# CP2102N.net
KiCad netlist of a schematic drawn in Altium Designer
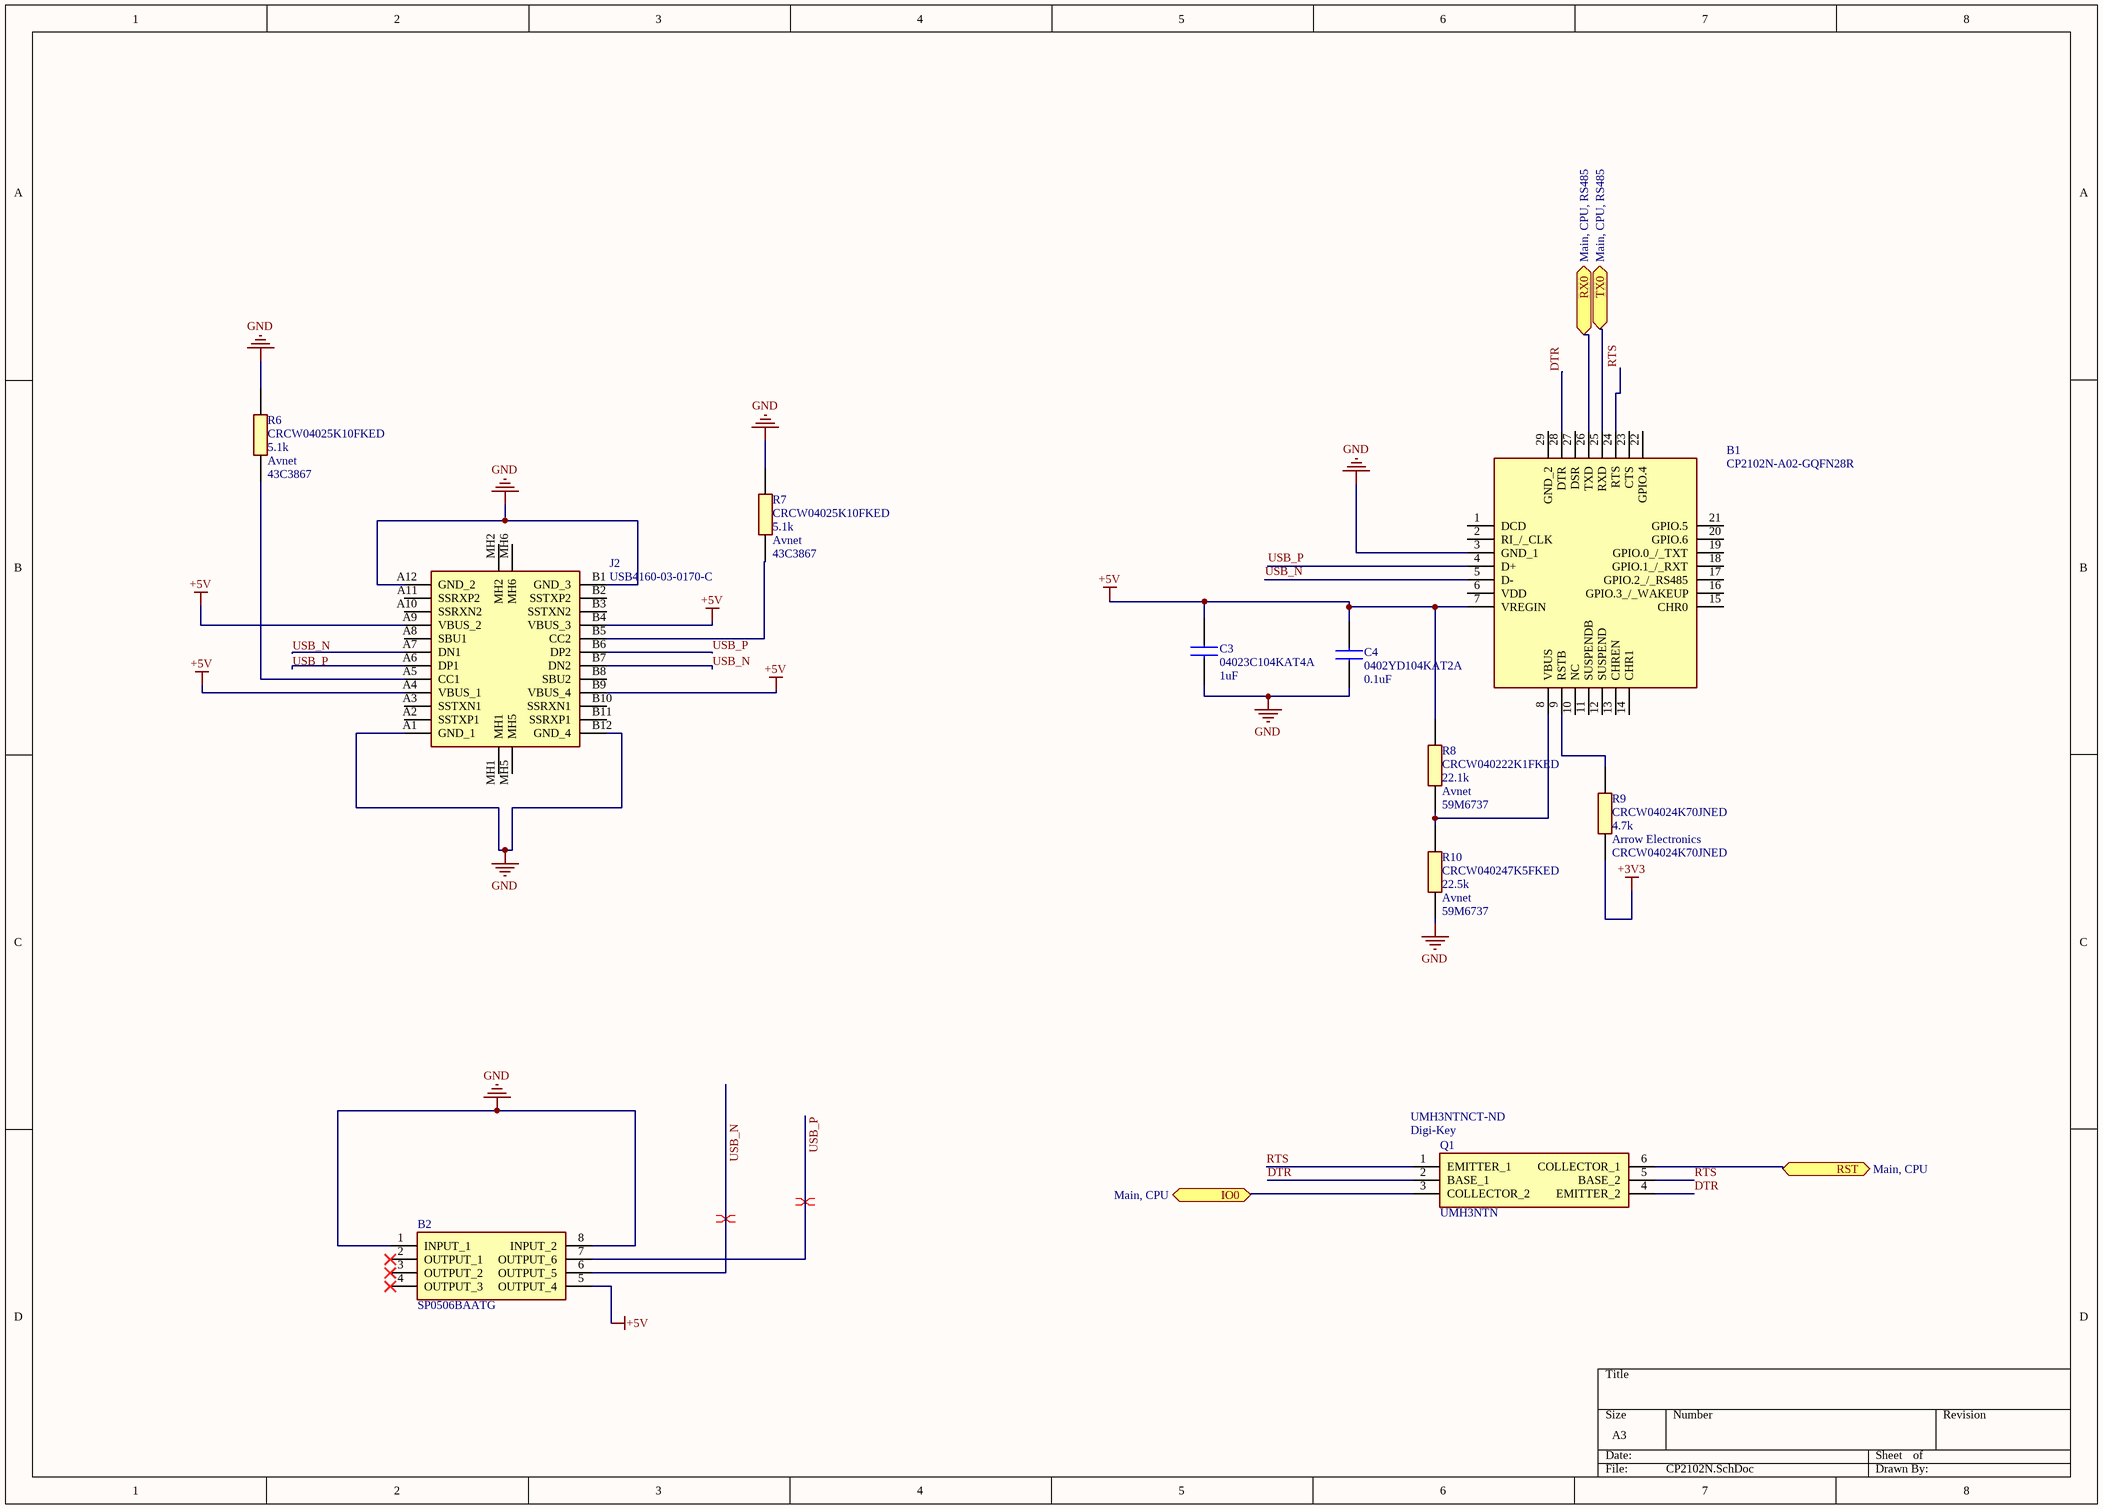
[diagram p0: CP2102N.SchDoc]

(export (version "E")
  (design (tool "Eeschema 10.0.6"))
  (components
    (comp (ref "B1")
      (value "CP2102N-A02-GQFN28R")
      (footprint "QFN50P500X500X80-29N-D")
      (description "USB Interface IC USB to UART bridge - QFN28")
      (fields (field (name "MOUSER PART NUMBER") "634-CP2102NA02QFN28R"))
      (libsource (lib "SFMproject") (part "CP2102N-A02-GQFN28R"))
    )
    (comp (ref "B2")
      (value "SP0506BAATG")
      (footprint "SOP65P488X117-8N")
      (description "TVS Diode Arrays")
      (fields (field (name "MOUSER PART NUMBER") "576-SP0506BAATG"))
      (libsource (lib "Cool@C_V2_lib_final") (part "SP0506BAATG"))
    )
    (comp (ref "C3")
      (value "04023C104KAT4A")
      (footprint "CAPC1005X40N")
      (description "Multilayer Ceramic Capacitors MLCC - SMD/SMT 25V .1uF X7R 0402")
      (fields (field (name "MOUSER PART NUMBER") "581-04023C104KAT4A") (field (name "ALTIUM_VALUE") "1uF"))
      (libsource (lib "Cool@C_V2_lib_final") (part "04023C104KAT4A"))
    )
    (comp (ref "C4")
      (value "0402YD104KAT2A")
      (footprint "CAPC1005X40N")
      (fields (field (name "MOUSER PART NUMBER") "581-0402YD104K") (field (name "ALTIUM_VALUE") "0.1uF"))
      (libsource (lib "Cool@C_V2_lib_final") (part "0402YD104KAT2A"))
    )
    (comp (ref "J2")
      (value "USB4160-03-0170-C")
      (footprint "USB4160030170C")
      (description "USB Connectors USB-C Rec 3u\" Vert 24P SMT 1.7mm TH stakes H7.46mm T+R+Cap")
      (fields (field (name "MOUSER PART NUMBER") "640-USB4160-3-0170-C"))
      (libsource (lib "SFMproject") (part "USB4160-03-0170-C"))
    )
    (comp (ref "Q1")
      (value "UMH3NTN")
      (footprint "UMH3NTN")
      (description "Bipolar Transistors - Pre-Biased DUAL NPN 50V 100MA SOT-363")
      (fields
        (field (name "MOUSER PART NUMBER") "755-UMH3NTN")
        (field (name "SUPPLIER 1") "Digi-Key")
        (field (name "SUPPLIER PART NUMBER 1") "UMH3NTNCT-ND")
      )
      (libsource (lib "Cool@C_V2_lib_final") (part "UMH3NTN"))
    )
    (comp (ref "R6")
      (value "CRCW04025K10FKED")
      (footprint "RESC1005X40N")
      (description "Thick Film Resistors - SMD 3/4watt 5.1Kohms 5%")
      (fields
        (field (name "MOUSER PART NUMBER") "71-CRCW0402-5.1K-E3")
        (field (name "ALTIUM_VALUE") "5.1k")
        (field (name "SUPPLIER 1") "Avnet")
        (field (name "SUPPLIER PART NUMBER 1") "43C3867")
      )
      (libsource (lib "SFMproject") (part "CRCW04025K10FKED"))
    )
    (comp (ref "R7")
      (value "CRCW04025K10FKED")
      (footprint "RESC1005X40N")
      (description "Thick Film Resistors - SMD 3/4watt 5.1Kohms 5%")
      (fields
        (field (name "MOUSER PART NUMBER") "71-CRCW0402-5.1K-E3")
        (field (name "ALTIUM_VALUE") "5.1k")
        (field (name "SUPPLIER 1") "Avnet")
        (field (name "SUPPLIER PART NUMBER 1") "43C3867")
      )
      (libsource (lib "SFMproject") (part "CRCW04025K10FKED"))
    )
    (comp (ref "R8")
      (value "CRCW040222K1FKED")
      (footprint "RESC1005X40N")
      (description "Résistances à couches épaisses - CMS 1/16watt 22.1Kohms 1%")
      (fields
        (field (name "MOUSER PART NUMBER") "71-CRCW0402-22.1K-E3")
        (field (name "ALTIUM_VALUE") "22.1k")
        (field (name "SUPPLIER 1") "Avnet")
        (field (name "SUPPLIER PART NUMBER 1") "59M6737")
      )
      (libsource (lib "SFMproject") (part "CRCW040222K1FKED"))
    )
    (comp (ref "R9")
      (value "CRCW04024K70JNED")
      (footprint "RESC1005X40N")
      (description "VISHAY - CRCW04024K70JNED - RES, THICK FILM, 4K7, 5%, 0.063W, 0402")
      (fields
        (field (name "MOUSER PART NUMBER") "71-CRCW0402J-4.7K-E3")
        (field (name "ALTIUM_VALUE") "4.7k")
        (field (name "SUPPLIER 1") "Arrow Electronics")
        (field (name "SUPPLIER PART NUMBER 1") "CRCW04024K70JNED")
      )
      (libsource (lib "SFMproject") (part "CRCW04024K70JNED"))
    )
    (comp (ref "R10")
      (value "CRCW040247K5FKED")
      (footprint "RESC1005X40N")
      (description "Résistances à couches épaisses - CMS 1/16watt 47.5Kohms 1%")
      (fields
        (field (name "MOUSER PART NUMBER") "71-CRCW0402-47.5K-E3")
        (field (name "ALTIUM_VALUE") "22.5k")
        (field (name "SUPPLIER 1") "Avnet")
        (field (name "SUPPLIER PART NUMBER 1") "59M6737")
      )
      (libsource (lib "SFMproject") (part "CRCW040247K5FKED"))
    )
  )
  (nets
    (net (code "1") (name "+3V3") (class "Default")
      (node (ref "R9") (pin "1") (pinfunction "1_1") (pintype "passive"))
    )
    (net (code "2") (name "+5V") (class "Default")
      (node (ref "B1") (pin "7") (pinfunction "VREGIN_7") (pintype "passive"))
      (node (ref "B2") (pin "5") (pinfunction "OUTPUT_4_5") (pintype "passive"))
      (node (ref "C3") (pin "2") (pinfunction "2_2") (pintype "passive"))
      (node (ref "C4") (pin "2") (pinfunction "2_2") (pintype "passive"))
      (node (ref "J2") (pin "A4") (pinfunction "VBUS_1_A4") (pintype "passive"))
      (node (ref "J2") (pin "A9") (pinfunction "VBUS_2_A9") (pintype "passive"))
      (node (ref "J2") (pin "B4") (pinfunction "VBUS_3_B4") (pintype "passive"))
      (node (ref "J2") (pin "B9") (pinfunction "VBUS_4_B9") (pintype "passive"))
      (node (ref "R8") (pin "2") (pinfunction "2_2") (pintype "passive"))
    )
    (net (code "3") (name "/DTR") (class "Default")
      (node (ref "B1") (pin "28") (pinfunction "DTR_28") (pintype "passive"))
      (node (ref "Q1") (pin "2") (pinfunction "BASE_1_2") (pintype "passive"))
      (node (ref "Q1") (pin "4") (pinfunction "EMITTER_2_4") (pintype "passive"))
    )
    (net (code "4") (name "/IO0") (class "Default")
      (node (ref "Q1") (pin "3") (pinfunction "COLLECTOR_2_3") (pintype "passive"))
    )
    (net (code "5") (name "/RST") (class "Default")
      (node (ref "Q1") (pin "6") (pinfunction "COLLECTOR_1_6") (pintype "passive"))
    )
    (net (code "6") (name "/RTS") (class "Default")
      (node (ref "B1") (pin "24") (pinfunction "RTS_24") (pintype "passive"))
      (node (ref "Q1") (pin "1") (pinfunction "EMITTER_1_1") (pintype "passive"))
      (node (ref "Q1") (pin "5") (pinfunction "BASE_2_5") (pintype "passive"))
    )
    (net (code "7") (name "/RX0") (class "Default")
      (node (ref "B1") (pin "26") (pinfunction "TXD_26") (pintype "passive"))
    )
    (net (code "8") (name "/TX0") (class "Default")
      (node (ref "B1") (pin "25") (pinfunction "RXD_25") (pintype "passive"))
    )
    (net (code "9") (name "/USB_N") (class "Default")
      (node (ref "B1") (pin "5") (pinfunction "D-_5") (pintype "passive"))
      (node (ref "B2") (pin "6") (pinfunction "OUTPUT_5_6") (pintype "passive"))
      (node (ref "J2") (pin "A7") (pinfunction "DN1_A7") (pintype "passive"))
      (node (ref "J2") (pin "B7") (pinfunction "DN2_B7") (pintype "passive"))
    )
    (net (code "10") (name "/USB_P") (class "Default")
      (node (ref "B1") (pin "4") (pinfunction "D+_4") (pintype "passive"))
      (node (ref "B2") (pin "7") (pinfunction "OUTPUT_6_7") (pintype "passive"))
      (node (ref "J2") (pin "A6") (pinfunction "DP1_A6") (pintype "passive"))
      (node (ref "J2") (pin "B6") (pinfunction "DP2_B6") (pintype "passive"))
    )
    (net (code "11") (name "GND") (class "Default")
      (node (ref "B1") (pin "3") (pinfunction "GND_1_3") (pintype "passive"))
      (node (ref "B2") (pin "1") (pinfunction "INPUT_1_1") (pintype "passive"))
      (node (ref "B2") (pin "8") (pinfunction "INPUT_2_8") (pintype "passive"))
      (node (ref "C3") (pin "1") (pinfunction "1_1") (pintype "passive"))
      (node (ref "C4") (pin "1") (pinfunction "1_1") (pintype "passive"))
      (node (ref "J2") (pin "A1") (pinfunction "GND_1_A1") (pintype "passive"))
      (node (ref "J2") (pin "A12") (pinfunction "GND_2_A12") (pintype "passive"))
      (node (ref "J2") (pin "B1") (pinfunction "GND_3_B1") (pintype "passive"))
      (node (ref "J2") (pin "B12") (pinfunction "GND_4_B12") (pintype "passive"))
      (node (ref "R10") (pin "1") (pinfunction "1_1") (pintype "passive"))
      (node (ref "R6") (pin "2") (pinfunction "2_2") (pintype "passive"))
      (node (ref "R7") (pin "2") (pinfunction "2_2") (pintype "passive"))
    )
    (net (code "12") (name "Net-(B1-RSTB)") (class "Default")
      (node (ref "B1") (pin "9") (pinfunction "RSTB_9") (pintype "passive"))
      (node (ref "R9") (pin "2") (pinfunction "2_2") (pintype "passive"))
    )
    (net (code "13") (name "Net-(B1-VBUS)") (class "Default")
      (node (ref "B1") (pin "8") (pinfunction "VBUS_8") (pintype "passive"))
      (node (ref "R10") (pin "2") (pinfunction "2_2") (pintype "passive"))
      (node (ref "R8") (pin "1") (pinfunction "1_1") (pintype "passive"))
    )
    (net (code "14") (name "Net-(J2-CC1)") (class "Default")
      (node (ref "J2") (pin "A5") (pinfunction "CC1_A5") (pintype "passive"))
      (node (ref "R6") (pin "1") (pinfunction "1_1") (pintype "passive"))
    )
    (net (code "15") (name "Net-(J2-CC2)") (class "Default")
      (node (ref "J2") (pin "B5") (pinfunction "CC2_B5") (pintype "passive"))
      (node (ref "R7") (pin "1") (pinfunction "1_1") (pintype "passive"))
    )
    (net (code "16") (name "unconnected-(B1-CHR0-Pad15)") (class "Default")
      (node (ref "B1") (pin "15") (pinfunction "CHR0_15") (pintype "passive"))
    )
    (net (code "17") (name "unconnected-(B1-CHR1-Pad14)") (class "Default")
      (node (ref "B1") (pin "14") (pinfunction "CHR1_14") (pintype "passive"))
    )
    (net (code "18") (name "unconnected-(B1-CHREN-Pad13)") (class "Default")
      (node (ref "B1") (pin "13") (pinfunction "CHREN_13") (pintype "passive"))
    )
    (net (code "19") (name "unconnected-(B1-CTS-Pad23)") (class "Default")
      (node (ref "B1") (pin "23") (pinfunction "CTS_23") (pintype "passive"))
    )
    (net (code "20") (name "unconnected-(B1-DCD-Pad1)") (class "Default")
      (node (ref "B1") (pin "1") (pinfunction "DCD_1") (pintype "passive"))
    )
    (net (code "21") (name "unconnected-(B1-DSR-Pad27)") (class "Default")
      (node (ref "B1") (pin "27") (pinfunction "DSR_27") (pintype "passive"))
    )
    (net (code "22") (name "unconnected-(B1-GND_2-Pad29)") (class "Default")
      (node (ref "B1") (pin "29") (pinfunction "GND_2_29") (pintype "passive"))
    )
    (net (code "23") (name "unconnected-(B1-GPIO.0_{slash}_TXT-Pad19)") (class "Default")
      (node (ref "B1") (pin "19") (pinfunction "GPIO.0_/_TXT_19") (pintype "passive"))
    )
    (net (code "24") (name "unconnected-(B1-GPIO.1_{slash}_RXT-Pad18)") (class "Default")
      (node (ref "B1") (pin "18") (pinfunction "GPIO.1_/_RXT_18") (pintype "passive"))
    )
    (net (code "25") (name "unconnected-(B1-GPIO.2_{slash}_RS485-Pad17)") (class "Default")
      (node (ref "B1") (pin "17") (pinfunction "GPIO.2_/_RS485_17") (pintype "passive"))
    )
    (net (code "26") (name "unconnected-(B1-GPIO.3_{slash}_WAKEUP-Pad16)") (class "Default")
      (node (ref "B1") (pin "16") (pinfunction "GPIO.3_/_WAKEUP_16") (pintype "passive"))
    )
    (net (code "27") (name "unconnected-(B1-GPIO.4-Pad22)") (class "Default")
      (node (ref "B1") (pin "22") (pinfunction "GPIO.4_22") (pintype "passive"))
    )
    (net (code "28") (name "unconnected-(B1-GPIO.5-Pad21)") (class "Default")
      (node (ref "B1") (pin "21") (pinfunction "GPIO.5_21") (pintype "passive"))
    )
    (net (code "29") (name "unconnected-(B1-GPIO.6-Pad20)") (class "Default")
      (node (ref "B1") (pin "20") (pinfunction "GPIO.6_20") (pintype "passive"))
    )
    (net (code "30") (name "unconnected-(B1-NC-Pad10)") (class "Default")
      (node (ref "B1") (pin "10") (pinfunction "NC_10") (pintype "passive"))
    )
    (net (code "31") (name "unconnected-(B1-RI_{slash}_CLK-Pad2)") (class "Default")
      (node (ref "B1") (pin "2") (pinfunction "RI_/_CLK_2") (pintype "passive"))
    )
    (net (code "32") (name "unconnected-(B1-SUSPEND-Pad12)") (class "Default")
      (node (ref "B1") (pin "12") (pinfunction "SUSPEND_12") (pintype "passive"))
    )
    (net (code "33") (name "unconnected-(B1-SUSPENDB-Pad11)") (class "Default")
      (node (ref "B1") (pin "11") (pinfunction "SUSPENDB_11") (pintype "passive"))
    )
    (net (code "34") (name "unconnected-(B1-VDD-Pad6)") (class "Default")
      (node (ref "B1") (pin "6") (pinfunction "VDD_6") (pintype "passive"))
    )
    (net (code "35") (name "unconnected-(B2-OUTPUT_1-Pad2)") (class "Default")
      (node (ref "B2") (pin "2") (pinfunction "OUTPUT_1_2") (pintype "passive+no_connect"))
    )
    (net (code "36") (name "unconnected-(B2-OUTPUT_2-Pad3)") (class "Default")
      (node (ref "B2") (pin "3") (pinfunction "OUTPUT_2_3") (pintype "passive+no_connect"))
    )
    (net (code "37") (name "unconnected-(B2-OUTPUT_3-Pad4)") (class "Default")
      (node (ref "B2") (pin "4") (pinfunction "OUTPUT_3_4") (pintype "passive+no_connect"))
    )
    (net (code "38") (name "unconnected-(J2-PadMH1)") (class "Default")
      (node (ref "J2") (pin "MH1") (pinfunction "MH1_MH1") (pintype "passive"))
    )
    (net (code "39") (name "unconnected-(J2-PadMH2)") (class "Default")
      (node (ref "J2") (pin "MH2") (pinfunction "MH2_MH2") (pintype "passive"))
    )
    (net (code "40") (name "unconnected-(J2-PadMH5)") (class "Default")
      (node (ref "J2") (pin "MH5") (pinfunction "MH5_MH5") (pintype "passive"))
    )
    (net (code "41") (name "unconnected-(J2-PadMH6)") (class "Default")
      (node (ref "J2") (pin "MH6") (pinfunction "MH6_MH6") (pintype "passive"))
    )
    (net (code "42") (name "unconnected-(J2-SBU1-PadA8)") (class "Default")
      (node (ref "J2") (pin "A8") (pinfunction "SBU1_A8") (pintype "passive"))
    )
    (net (code "43") (name "unconnected-(J2-SBU2-PadB8)") (class "Default")
      (node (ref "J2") (pin "B8") (pinfunction "SBU2_B8") (pintype "passive"))
    )
    (net (code "44") (name "unconnected-(J2-SSRXN1-PadB10)") (class "Default")
      (node (ref "J2") (pin "B10") (pinfunction "SSRXN1_B10") (pintype "passive"))
    )
    (net (code "45") (name "unconnected-(J2-SSRXN2-PadA10)") (class "Default")
      (node (ref "J2") (pin "A10") (pinfunction "SSRXN2_A10") (pintype "passive"))
    )
    (net (code "46") (name "unconnected-(J2-SSRXP1-PadB11)") (class "Default")
      (node (ref "J2") (pin "B11") (pinfunction "SSRXP1_B11") (pintype "passive"))
    )
    (net (code "47") (name "unconnected-(J2-SSRXP2-PadA11)") (class "Default")
      (node (ref "J2") (pin "A11") (pinfunction "SSRXP2_A11") (pintype "passive"))
    )
    (net (code "48") (name "unconnected-(J2-SSTXN1-PadA3)") (class "Default")
      (node (ref "J2") (pin "A3") (pinfunction "SSTXN1_A3") (pintype "passive"))
    )
    (net (code "49") (name "unconnected-(J2-SSTXN2-PadB3)") (class "Default")
      (node (ref "J2") (pin "B3") (pinfunction "SSTXN2_B3") (pintype "passive"))
    )
    (net (code "50") (name "unconnected-(J2-SSTXP1-PadA2)") (class "Default")
      (node (ref "J2") (pin "A2") (pinfunction "SSTXP1_A2") (pintype "passive"))
    )
    (net (code "51") (name "unconnected-(J2-SSTXP2-PadB2)") (class "Default")
      (node (ref "J2") (pin "B2") (pinfunction "SSTXP2_B2") (pintype "passive"))
    )
  )
)
